# LilyPad_Protoboard_Large.net
KiCad netlist of a schematic drawn in EAGLE
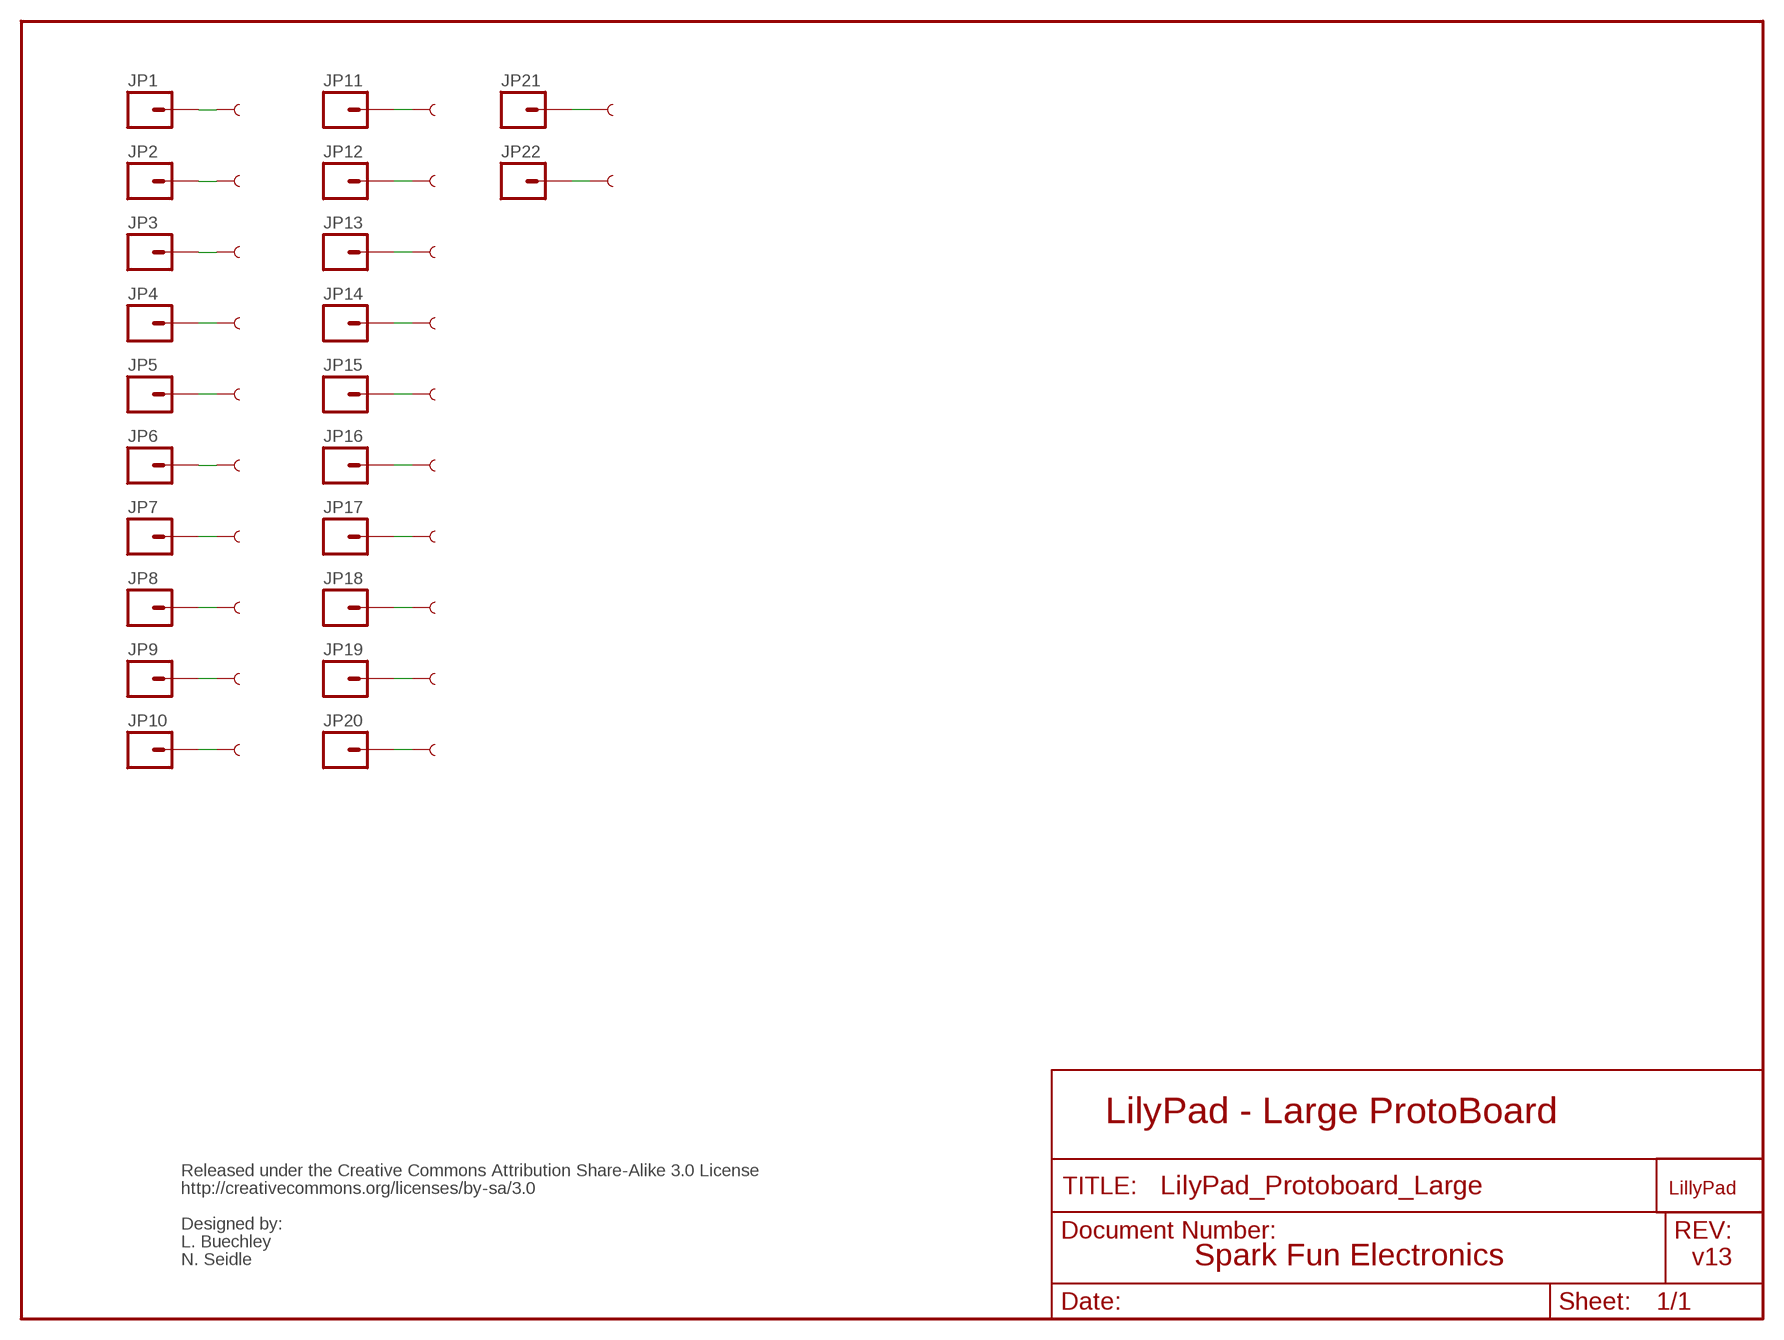
[diagram p0: schematic, sheet 1]

(export (version "E")
  (design (tool "Eeschema 10.0.6"))
  (components
    (comp (ref "GND")
      (value "SEWTAP9")
      (footprint "eagle-import:PETAL-LONG-1-2SIDE")
      (libsource (lib "eagle-import") (part "SEWTAP9"))
    )
    (comp (ref "JP1")
      (value "M01SMDNS")
      (footprint "eagle-import:1X01NS")
      (libsource (lib "eagle-import") (part "M01SMDNS"))
    )
    (comp (ref "JP2")
      (value "M01SMDNS")
      (footprint "eagle-import:1X01NS")
      (libsource (lib "eagle-import") (part "M01SMDNS"))
    )
    (comp (ref "JP3")
      (value "M01SMDNS")
      (footprint "eagle-import:1X01NS")
      (libsource (lib "eagle-import") (part "M01SMDNS"))
    )
    (comp (ref "JP4")
      (value "M01SMDNS")
      (footprint "eagle-import:1X01NS")
      (libsource (lib "eagle-import") (part "M01SMDNS"))
    )
    (comp (ref "JP5")
      (value "M01SMDNS")
      (footprint "eagle-import:1X01NS")
      (libsource (lib "eagle-import") (part "M01SMDNS"))
    )
    (comp (ref "JP6")
      (value "M01SMDNS")
      (footprint "eagle-import:1X01NS")
      (libsource (lib "eagle-import") (part "M01SMDNS"))
    )
    (comp (ref "JP7")
      (value "M01SMDNS")
      (footprint "eagle-import:1X01NS")
      (libsource (lib "eagle-import") (part "M01SMDNS"))
    )
    (comp (ref "JP8")
      (value "M01SMDNS")
      (footprint "eagle-import:1X01NS")
      (libsource (lib "eagle-import") (part "M01SMDNS"))
    )
    (comp (ref "JP9")
      (value "M01SMDNS")
      (footprint "eagle-import:1X01NS")
      (libsource (lib "eagle-import") (part "M01SMDNS"))
    )
    (comp (ref "JP10")
      (value "M01SMDNS")
      (footprint "eagle-import:1X01NS")
      (libsource (lib "eagle-import") (part "M01SMDNS"))
    )
    (comp (ref "JP11")
      (value "M01SMDNS")
      (footprint "eagle-import:1X01NS")
      (libsource (lib "eagle-import") (part "M01SMDNS"))
    )
    (comp (ref "JP12")
      (value "M01SMDNS")
      (footprint "eagle-import:1X01NS")
      (libsource (lib "eagle-import") (part "M01SMDNS"))
    )
    (comp (ref "JP13")
      (value "M01SMDNS")
      (footprint "eagle-import:1X01NS")
      (libsource (lib "eagle-import") (part "M01SMDNS"))
    )
    (comp (ref "JP14")
      (value "M01SMDNS")
      (footprint "eagle-import:1X01NS")
      (libsource (lib "eagle-import") (part "M01SMDNS"))
    )
    (comp (ref "JP15")
      (value "M01SMDNS")
      (footprint "eagle-import:1X01NS")
      (libsource (lib "eagle-import") (part "M01SMDNS"))
    )
    (comp (ref "JP16")
      (value "M01SMDNS")
      (footprint "eagle-import:1X01NS")
      (libsource (lib "eagle-import") (part "M01SMDNS"))
    )
    (comp (ref "JP17")
      (value "M01SMDNS")
      (footprint "eagle-import:1X01NS")
      (libsource (lib "eagle-import") (part "M01SMDNS"))
    )
    (comp (ref "JP18")
      (value "M01SMDNS")
      (footprint "eagle-import:1X01NS")
      (libsource (lib "eagle-import") (part "M01SMDNS"))
    )
    (comp (ref "JP19")
      (value "M01SMDNS")
      (footprint "eagle-import:1X01NS")
      (libsource (lib "eagle-import") (part "M01SMDNS"))
    )
    (comp (ref "JP20")
      (value "M01SMDNS")
      (footprint "eagle-import:1X01NS")
      (libsource (lib "eagle-import") (part "M01SMDNS"))
    )
    (comp (ref "JP21")
      (value "M01SMDNS")
      (footprint "eagle-import:1X01NS")
      (libsource (lib "eagle-import") (part "M01SMDNS"))
    )
    (comp (ref "JP22")
      (value "M01SMDNS")
      (footprint "eagle-import:1X01NS")
      (libsource (lib "eagle-import") (part "M01SMDNS"))
    )
    (comp (ref "U$2")
      (value "LOGO-LPL")
      (footprint "eagle-import:LOGO-L")
      (libsource (lib "eagle-import") (part "LOGO-LPL"))
    )
    (comp (ref "U$4")
      (value "SEWTAP9")
      (footprint "eagle-import:PETAL-LONG-1-2SIDE")
      (libsource (lib "eagle-import") (part "SEWTAP9"))
    )
    (comp (ref "U$30")
      (value "SEWTAP9")
      (footprint "eagle-import:PETAL-LONG-1-2SIDE")
      (libsource (lib "eagle-import") (part "SEWTAP9"))
    )
    (comp (ref "U$31")
      (value "SEWTAP9")
      (footprint "eagle-import:PETAL-LONG-1-2SIDE")
      (libsource (lib "eagle-import") (part "SEWTAP9"))
    )
    (comp (ref "U$32")
      (value "SEWTAP9")
      (footprint "eagle-import:PETAL-LONG-1-2SIDE")
      (libsource (lib "eagle-import") (part "SEWTAP9"))
    )
    (comp (ref "U$33")
      (value "SEWTAP9")
      (footprint "eagle-import:PETAL-LONG-1-2SIDE")
      (libsource (lib "eagle-import") (part "SEWTAP9"))
    )
    (comp (ref "U$34")
      (value "SEWTAP9")
      (footprint "eagle-import:PETAL-LONG-1-2SIDE")
      (libsource (lib "eagle-import") (part "SEWTAP9"))
    )
    (comp (ref "U$35")
      (value "SEWTAP9")
      (footprint "eagle-import:PETAL-LONG-1-2SIDE")
      (libsource (lib "eagle-import") (part "SEWTAP9"))
    )
    (comp (ref "U$36")
      (value "SEWTAP9")
      (footprint "eagle-import:PETAL-LONG-1-2SIDE")
      (libsource (lib "eagle-import") (part "SEWTAP9"))
    )
    (comp (ref "U$37")
      (value "SEWTAP9")
      (footprint "eagle-import:PETAL-LONG-1-2SIDE")
      (libsource (lib "eagle-import") (part "SEWTAP9"))
    )
    (comp (ref "U$38")
      (value "SEWTAP9")
      (footprint "eagle-import:PETAL-LONG-1-2SIDE")
      (libsource (lib "eagle-import") (part "SEWTAP9"))
    )
    (comp (ref "U$39")
      (value "SEWTAP9")
      (footprint "eagle-import:PETAL-LONG-1-2SIDE")
      (libsource (lib "eagle-import") (part "SEWTAP9"))
    )
    (comp (ref "U$40")
      (value "SEWTAP9")
      (footprint "eagle-import:PETAL-LONG-1-2SIDE")
      (libsource (lib "eagle-import") (part "SEWTAP9"))
    )
    (comp (ref "U$41")
      (value "SEWTAP9")
      (footprint "eagle-import:PETAL-LONG-1-2SIDE")
      (libsource (lib "eagle-import") (part "SEWTAP9"))
    )
    (comp (ref "U$42")
      (value "SEWTAP9")
      (footprint "eagle-import:PETAL-LONG-1-2SIDE")
      (libsource (lib "eagle-import") (part "SEWTAP9"))
    )
    (comp (ref "U$43")
      (value "SEWTAP9")
      (footprint "eagle-import:PETAL-LONG-1-2SIDE")
      (libsource (lib "eagle-import") (part "SEWTAP9"))
    )
    (comp (ref "U$44")
      (value "SEWTAP9")
      (footprint "eagle-import:PETAL-LONG-1-2SIDE")
      (libsource (lib "eagle-import") (part "SEWTAP9"))
    )
    (comp (ref "U$45")
      (value "SEWTAP9")
      (footprint "eagle-import:PETAL-LONG-1-2SIDE")
      (libsource (lib "eagle-import") (part "SEWTAP9"))
    )
    (comp (ref "U$46")
      (value "SEWTAP9")
      (footprint "eagle-import:PETAL-LONG-1-2SIDE")
      (libsource (lib "eagle-import") (part "SEWTAP9"))
    )
    (comp (ref "U$47")
      (value "SEWTAP9")
      (footprint "eagle-import:PETAL-LONG-1-2SIDE")
      (libsource (lib "eagle-import") (part "SEWTAP9"))
    )
    (comp (ref "U$48")
      (value "SEWTAP9")
      (footprint "eagle-import:PETAL-LONG-1-2SIDE")
      (libsource (lib "eagle-import") (part "SEWTAP9"))
    )
    (comp (ref "U$51")
      (value "SEWTAP9")
      (footprint "eagle-import:PETAL-LONG-1-2SIDE")
      (libsource (lib "eagle-import") (part "SEWTAP9"))
    )
  )
  (nets
    (net (code "1") (name "/ALLNET") (class "Default")
      (node (ref "GND") (pin "1") (pinfunction "1_1") (pintype "bidirectional"))
      (node (ref "JP1") (pin "1") (pinfunction "1_1") (pintype "passive"))
      (node (ref "JP10") (pin "1") (pinfunction "1_1") (pintype "passive"))
      (node (ref "JP11") (pin "1") (pinfunction "1_1") (pintype "passive"))
      (node (ref "JP12") (pin "1") (pinfunction "1_1") (pintype "passive"))
      (node (ref "JP13") (pin "1") (pinfunction "1_1") (pintype "passive"))
      (node (ref "JP14") (pin "1") (pinfunction "1_1") (pintype "passive"))
      (node (ref "JP15") (pin "1") (pinfunction "1_1") (pintype "passive"))
      (node (ref "JP16") (pin "1") (pinfunction "1_1") (pintype "passive"))
      (node (ref "JP17") (pin "1") (pinfunction "1_1") (pintype "passive"))
      (node (ref "JP18") (pin "1") (pinfunction "1_1") (pintype "passive"))
      (node (ref "JP19") (pin "1") (pinfunction "1_1") (pintype "passive"))
      (node (ref "JP2") (pin "1") (pinfunction "1_1") (pintype "passive"))
      (node (ref "JP20") (pin "1") (pinfunction "1_1") (pintype "passive"))
      (node (ref "JP21") (pin "1") (pinfunction "1_1") (pintype "passive"))
      (node (ref "JP22") (pin "1") (pinfunction "1_1") (pintype "passive"))
      (node (ref "JP3") (pin "1") (pinfunction "1_1") (pintype "passive"))
      (node (ref "JP4") (pin "1") (pinfunction "1_1") (pintype "passive"))
      (node (ref "JP5") (pin "1") (pinfunction "1_1") (pintype "passive"))
      (node (ref "JP6") (pin "1") (pinfunction "1_1") (pintype "passive"))
      (node (ref "JP7") (pin "1") (pinfunction "1_1") (pintype "passive"))
      (node (ref "JP8") (pin "1") (pinfunction "1_1") (pintype "passive"))
      (node (ref "JP9") (pin "1") (pinfunction "1_1") (pintype "passive"))
      (node (ref "U$30") (pin "1") (pinfunction "1_1") (pintype "bidirectional"))
      (node (ref "U$31") (pin "1") (pinfunction "1_1") (pintype "bidirectional"))
      (node (ref "U$32") (pin "1") (pinfunction "1_1") (pintype "bidirectional"))
      (node (ref "U$33") (pin "1") (pinfunction "1_1") (pintype "bidirectional"))
      (node (ref "U$34") (pin "1") (pinfunction "1_1") (pintype "bidirectional"))
      (node (ref "U$35") (pin "1") (pinfunction "1_1") (pintype "bidirectional"))
      (node (ref "U$36") (pin "1") (pinfunction "1_1") (pintype "bidirectional"))
      (node (ref "U$37") (pin "1") (pinfunction "1_1") (pintype "bidirectional"))
      (node (ref "U$38") (pin "1") (pinfunction "1_1") (pintype "bidirectional"))
      (node (ref "U$39") (pin "1") (pinfunction "1_1") (pintype "bidirectional"))
      (node (ref "U$4") (pin "1") (pinfunction "1_1") (pintype "bidirectional"))
      (node (ref "U$40") (pin "1") (pinfunction "1_1") (pintype "bidirectional"))
      (node (ref "U$41") (pin "1") (pinfunction "1_1") (pintype "bidirectional"))
      (node (ref "U$42") (pin "1") (pinfunction "1_1") (pintype "bidirectional"))
      (node (ref "U$43") (pin "1") (pinfunction "1_1") (pintype "bidirectional"))
      (node (ref "U$44") (pin "1") (pinfunction "1_1") (pintype "bidirectional"))
      (node (ref "U$45") (pin "1") (pinfunction "1_1") (pintype "bidirectional"))
      (node (ref "U$46") (pin "1") (pinfunction "1_1") (pintype "bidirectional"))
      (node (ref "U$47") (pin "1") (pinfunction "1_1") (pintype "bidirectional"))
      (node (ref "U$48") (pin "1") (pinfunction "1_1") (pintype "bidirectional"))
      (node (ref "U$51") (pin "1") (pinfunction "1_1") (pintype "bidirectional"))
    )
  )
)
